# Stepper_1_0.net
KiCad netlist of a schematic drawn in EAGLE
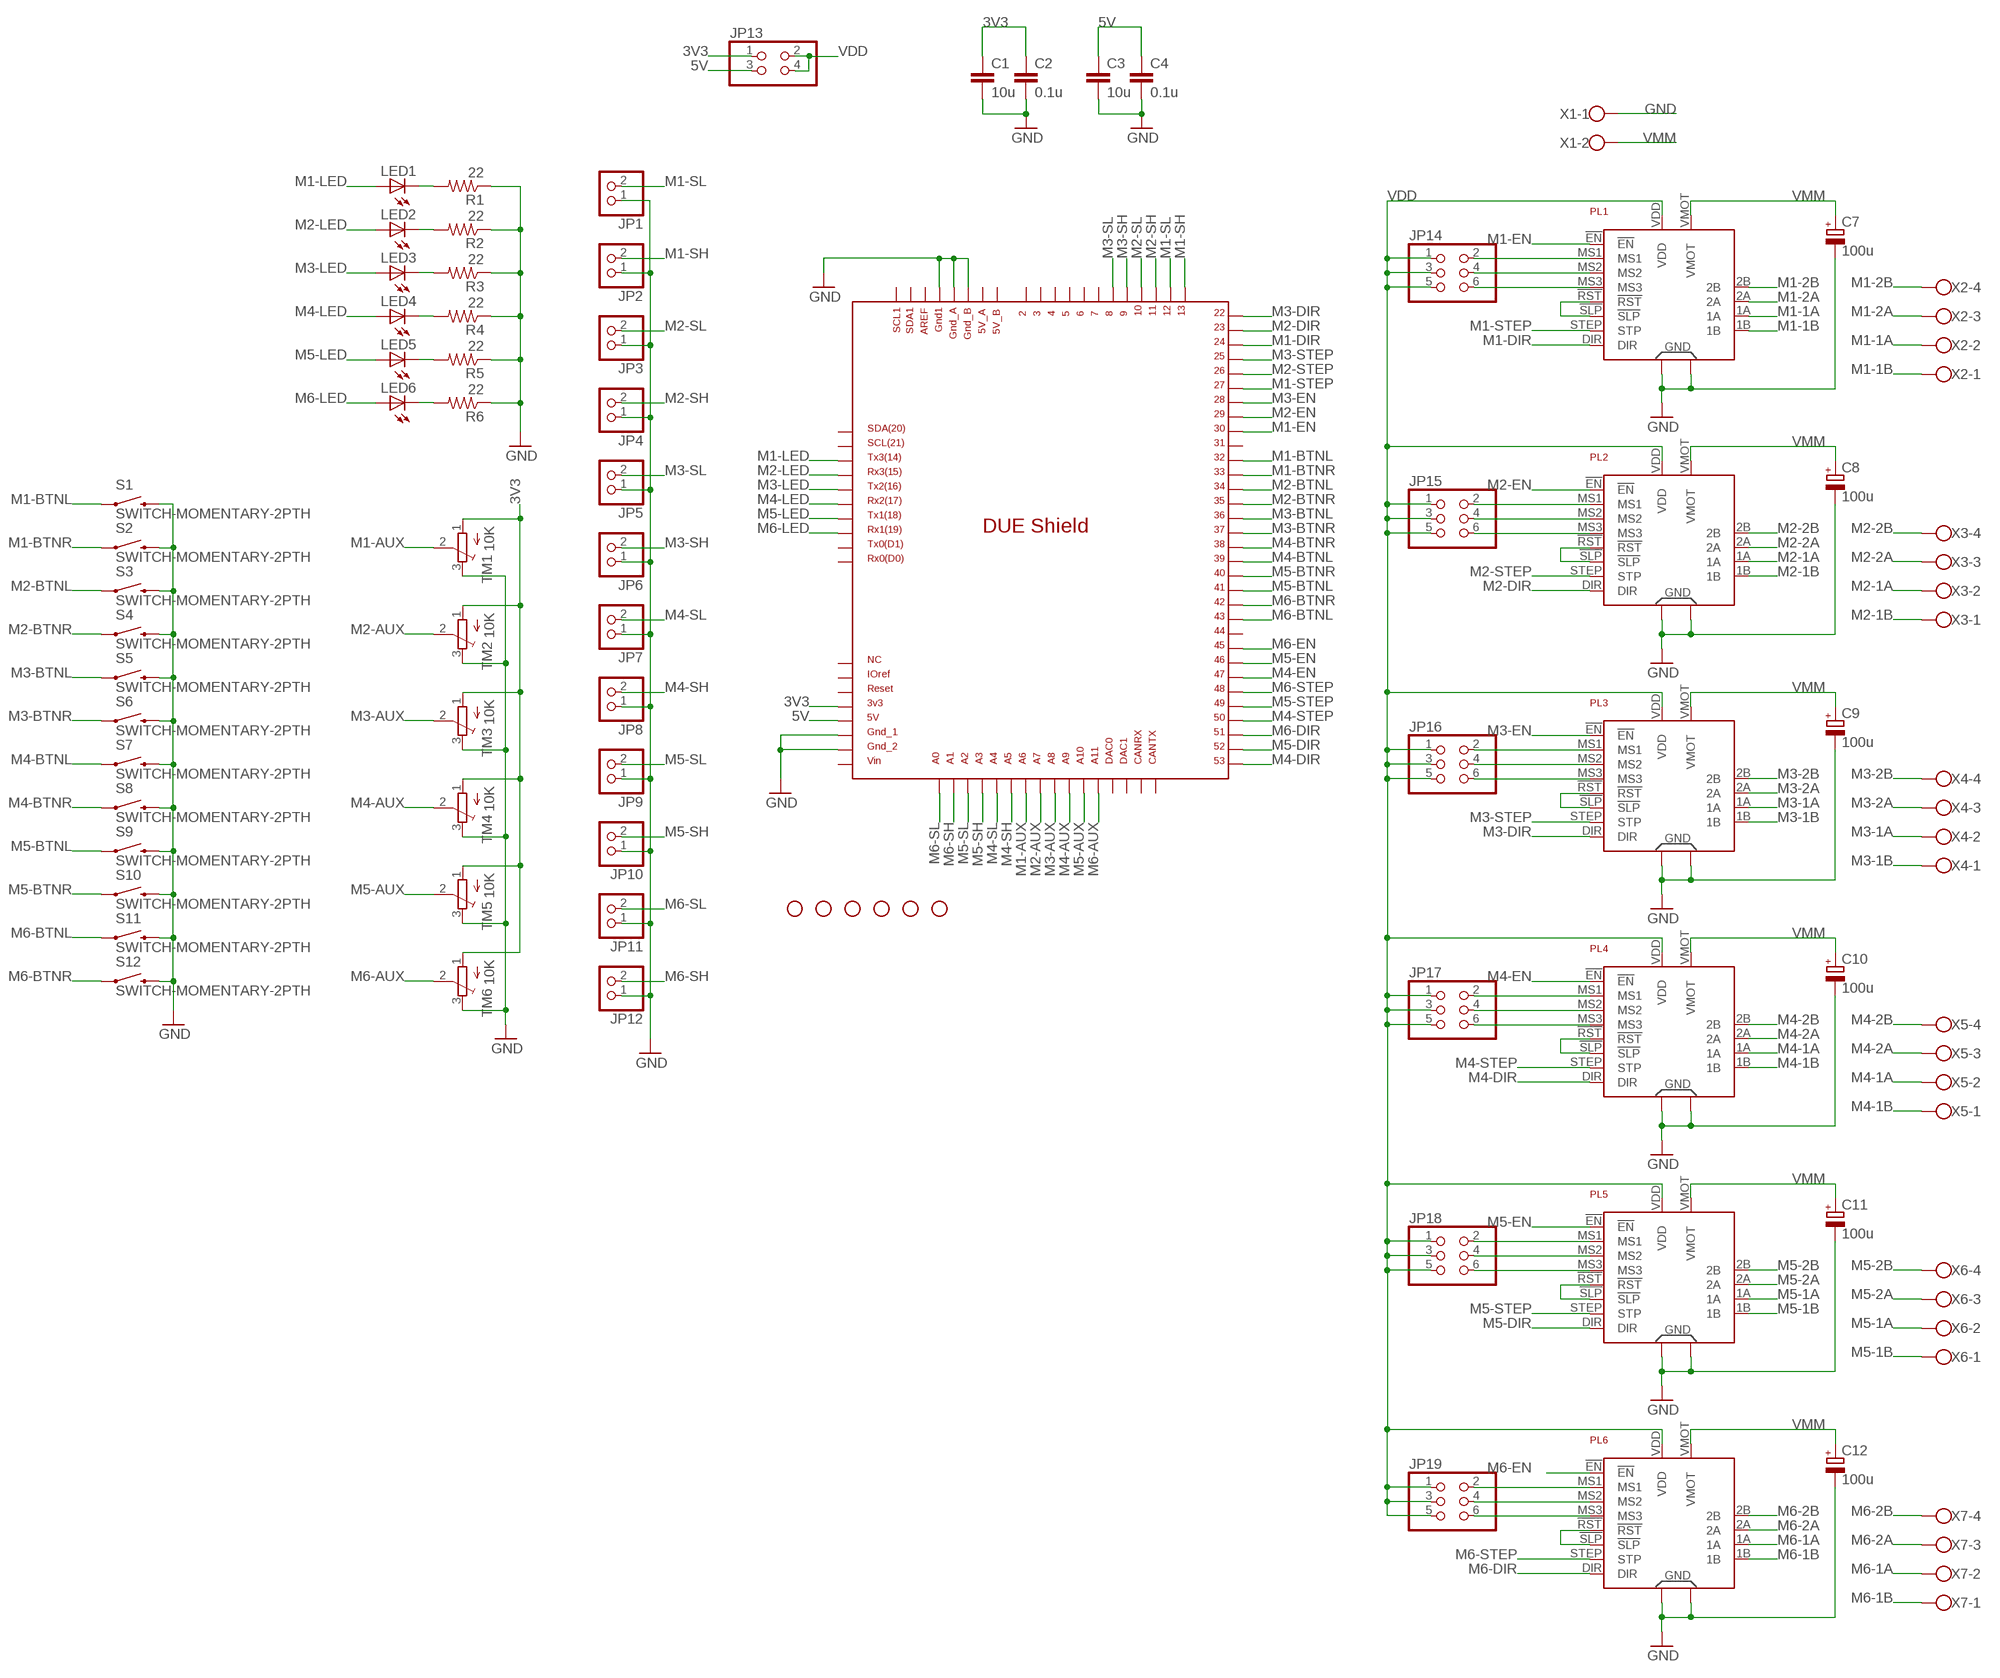
[diagram p0: schematic, sheet 1]

(export (version "E")
  (design (tool "Eeschema 10.0.6"))
  (components
    (comp (ref "C1")
      (value "10u")
      (footprint "eagle-import:1206")
      (libsource (lib "eagle-import") (part "CAP1206"))
    )
    (comp (ref "C2")
      (value "0.1u")
      (footprint "eagle-import:1206")
      (libsource (lib "eagle-import") (part "CAP1206"))
    )
    (comp (ref "C3")
      (value "10u")
      (footprint "eagle-import:1206")
      (libsource (lib "eagle-import") (part "CAP1206"))
    )
    (comp (ref "C4")
      (value "0.1u")
      (footprint "eagle-import:1206")
      (libsource (lib "eagle-import") (part "CAP1206"))
    )
    (comp (ref "C7")
      (value "100u")
      (footprint "eagle-import:ETR2")
      (libsource (lib "eagle-import") (part "CPOL-EUETR2"))
    )
    (comp (ref "C8")
      (value "100u")
      (footprint "eagle-import:ETR2")
      (libsource (lib "eagle-import") (part "CPOL-EUETR2"))
    )
    (comp (ref "C9")
      (value "100u")
      (footprint "eagle-import:ETR2")
      (libsource (lib "eagle-import") (part "CPOL-EUETR2"))
    )
    (comp (ref "C10")
      (value "100u")
      (footprint "eagle-import:ETR2")
      (libsource (lib "eagle-import") (part "CPOL-EUETR2"))
    )
    (comp (ref "C11")
      (value "100u")
      (footprint "eagle-import:ETR2")
      (libsource (lib "eagle-import") (part "CPOL-EUETR2"))
    )
    (comp (ref "C12")
      (value "100u")
      (footprint "eagle-import:ETR2")
      (libsource (lib "eagle-import") (part "CPOL-EUETR2"))
    )
    (comp (ref "H1")
      (value "STAND-OFF")
      (footprint "eagle-import:STAND-OFF")
      (libsource (lib "eagle-import") (part "STAND-OFF"))
    )
    (comp (ref "H2")
      (value "STAND-OFF")
      (footprint "eagle-import:STAND-OFF")
      (libsource (lib "eagle-import") (part "STAND-OFF"))
    )
    (comp (ref "H3")
      (value "STAND-OFF")
      (footprint "eagle-import:STAND-OFF")
      (libsource (lib "eagle-import") (part "STAND-OFF"))
    )
    (comp (ref "H4")
      (value "STAND-OFF")
      (footprint "eagle-import:STAND-OFF")
      (libsource (lib "eagle-import") (part "STAND-OFF"))
    )
    (comp (ref "H5")
      (value "STAND-OFF")
      (footprint "eagle-import:STAND-OFF")
      (libsource (lib "eagle-import") (part "STAND-OFF"))
    )
    (comp (ref "H6")
      (value "STAND-OFF")
      (footprint "eagle-import:STAND-OFF")
      (libsource (lib "eagle-import") (part "STAND-OFF"))
    )
    (comp (ref "JP1")
      (value "PINHD-1X2")
      (footprint "eagle-import:1X02")
      (libsource (lib "eagle-import") (part "PINHD-1X2"))
    )
    (comp (ref "JP2")
      (value "PINHD-1X2")
      (footprint "eagle-import:1X02")
      (libsource (lib "eagle-import") (part "PINHD-1X2"))
    )
    (comp (ref "JP3")
      (value "PINHD-1X2")
      (footprint "eagle-import:1X02")
      (libsource (lib "eagle-import") (part "PINHD-1X2"))
    )
    (comp (ref "JP4")
      (value "PINHD-1X2")
      (footprint "eagle-import:1X02")
      (libsource (lib "eagle-import") (part "PINHD-1X2"))
    )
    (comp (ref "JP5")
      (value "PINHD-1X2")
      (footprint "eagle-import:1X02")
      (libsource (lib "eagle-import") (part "PINHD-1X2"))
    )
    (comp (ref "JP6")
      (value "PINHD-1X2")
      (footprint "eagle-import:1X02")
      (libsource (lib "eagle-import") (part "PINHD-1X2"))
    )
    (comp (ref "JP7")
      (value "PINHD-1X2")
      (footprint "eagle-import:1X02")
      (libsource (lib "eagle-import") (part "PINHD-1X2"))
    )
    (comp (ref "JP8")
      (value "PINHD-1X2")
      (footprint "eagle-import:1X02")
      (libsource (lib "eagle-import") (part "PINHD-1X2"))
    )
    (comp (ref "JP9")
      (value "PINHD-1X2")
      (footprint "eagle-import:1X02")
      (libsource (lib "eagle-import") (part "PINHD-1X2"))
    )
    (comp (ref "JP10")
      (value "PINHD-1X2")
      (footprint "eagle-import:1X02")
      (libsource (lib "eagle-import") (part "PINHD-1X2"))
    )
    (comp (ref "JP11")
      (value "PINHD-1X2")
      (footprint "eagle-import:1X02")
      (libsource (lib "eagle-import") (part "PINHD-1X2"))
    )
    (comp (ref "JP12")
      (value "PINHD-1X2")
      (footprint "eagle-import:1X02")
      (libsource (lib "eagle-import") (part "PINHD-1X2"))
    )
    (comp (ref "JP13")
      (value "PINHD-2X2")
      (footprint "eagle-import:2X02")
      (libsource (lib "eagle-import") (part "PINHD-2X2"))
    )
    (comp (ref "JP14")
      (value "PINHD-2X3")
      (footprint "eagle-import:2X03")
      (libsource (lib "eagle-import") (part "PINHD-2X3"))
    )
    (comp (ref "JP15")
      (value "PINHD-2X3")
      (footprint "eagle-import:2X03")
      (libsource (lib "eagle-import") (part "PINHD-2X3"))
    )
    (comp (ref "JP16")
      (value "PINHD-2X3")
      (footprint "eagle-import:2X03")
      (libsource (lib "eagle-import") (part "PINHD-2X3"))
    )
    (comp (ref "JP17")
      (value "PINHD-2X3")
      (footprint "eagle-import:2X03")
      (libsource (lib "eagle-import") (part "PINHD-2X3"))
    )
    (comp (ref "JP18")
      (value "PINHD-2X3")
      (footprint "eagle-import:2X03")
      (libsource (lib "eagle-import") (part "PINHD-2X3"))
    )
    (comp (ref "JP19")
      (value "PINHD-2X3")
      (footprint "eagle-import:2X03")
      (libsource (lib "eagle-import") (part "PINHD-2X3"))
    )
    (comp (ref "LED1")
      (value "LEDSMT1206")
      (footprint "eagle-import:1206")
      (libsource (lib "eagle-import") (part "LEDSMT1206"))
    )
    (comp (ref "LED2")
      (value "LEDSMT1206")
      (footprint "eagle-import:1206")
      (libsource (lib "eagle-import") (part "LEDSMT1206"))
    )
    (comp (ref "LED3")
      (value "LEDSMT1206")
      (footprint "eagle-import:1206")
      (libsource (lib "eagle-import") (part "LEDSMT1206"))
    )
    (comp (ref "LED4")
      (value "LEDSMT1206")
      (footprint "eagle-import:1206")
      (libsource (lib "eagle-import") (part "LEDSMT1206"))
    )
    (comp (ref "LED5")
      (value "LEDSMT1206")
      (footprint "eagle-import:1206")
      (libsource (lib "eagle-import") (part "LEDSMT1206"))
    )
    (comp (ref "LED6")
      (value "LEDSMT1206")
      (footprint "eagle-import:1206")
      (libsource (lib "eagle-import") (part "LEDSMT1206"))
    )
    (comp (ref "PL1")
      (value "A4988X")
      (footprint "eagle-import:MD09X")
      (libsource (lib "eagle-import") (part "A4988X"))
    )
    (comp (ref "PL2")
      (value "A4988X")
      (footprint "eagle-import:MD09X")
      (libsource (lib "eagle-import") (part "A4988X"))
    )
    (comp (ref "PL3")
      (value "A4988X")
      (footprint "eagle-import:MD09X")
      (libsource (lib "eagle-import") (part "A4988X"))
    )
    (comp (ref "PL4")
      (value "A4988X")
      (footprint "eagle-import:MD09X")
      (libsource (lib "eagle-import") (part "A4988X"))
    )
    (comp (ref "PL5")
      (value "A4988X")
      (footprint "eagle-import:MD09X")
      (libsource (lib "eagle-import") (part "A4988X"))
    )
    (comp (ref "PL6")
      (value "A4988X")
      (footprint "eagle-import:MD09X")
      (libsource (lib "eagle-import") (part "A4988X"))
    )
    (comp (ref "R1")
      (value "22")
      (footprint "eagle-import:1206")
      (libsource (lib "eagle-import") (part "RESISTOR1206"))
    )
    (comp (ref "R2")
      (value "22")
      (footprint "eagle-import:1206")
      (libsource (lib "eagle-import") (part "RESISTOR1206"))
    )
    (comp (ref "R3")
      (value "22")
      (footprint "eagle-import:1206")
      (libsource (lib "eagle-import") (part "RESISTOR1206"))
    )
    (comp (ref "R4")
      (value "22")
      (footprint "eagle-import:1206")
      (libsource (lib "eagle-import") (part "RESISTOR1206"))
    )
    (comp (ref "R5")
      (value "22")
      (footprint "eagle-import:1206")
      (libsource (lib "eagle-import") (part "RESISTOR1206"))
    )
    (comp (ref "R6")
      (value "22")
      (footprint "eagle-import:1206")
      (libsource (lib "eagle-import") (part "RESISTOR1206"))
    )
    (comp (ref "S1")
      (value "SWITCH-MOMENTARY-2PTH")
      (footprint "eagle-import:TACTILE-PTH")
      (libsource (lib "eagle-import") (part "SWITCH-MOMENTARY-2PTH"))
    )
    (comp (ref "S2")
      (value "SWITCH-MOMENTARY-2PTH")
      (footprint "eagle-import:TACTILE-PTH")
      (libsource (lib "eagle-import") (part "SWITCH-MOMENTARY-2PTH"))
    )
    (comp (ref "S3")
      (value "SWITCH-MOMENTARY-2PTH")
      (footprint "eagle-import:TACTILE-PTH")
      (libsource (lib "eagle-import") (part "SWITCH-MOMENTARY-2PTH"))
    )
    (comp (ref "S4")
      (value "SWITCH-MOMENTARY-2PTH")
      (footprint "eagle-import:TACTILE-PTH")
      (libsource (lib "eagle-import") (part "SWITCH-MOMENTARY-2PTH"))
    )
    (comp (ref "S5")
      (value "SWITCH-MOMENTARY-2PTH")
      (footprint "eagle-import:TACTILE-PTH")
      (libsource (lib "eagle-import") (part "SWITCH-MOMENTARY-2PTH"))
    )
    (comp (ref "S6")
      (value "SWITCH-MOMENTARY-2PTH")
      (footprint "eagle-import:TACTILE-PTH")
      (libsource (lib "eagle-import") (part "SWITCH-MOMENTARY-2PTH"))
    )
    (comp (ref "S7")
      (value "SWITCH-MOMENTARY-2PTH")
      (footprint "eagle-import:TACTILE-PTH")
      (libsource (lib "eagle-import") (part "SWITCH-MOMENTARY-2PTH"))
    )
    (comp (ref "S8")
      (value "SWITCH-MOMENTARY-2PTH")
      (footprint "eagle-import:TACTILE-PTH")
      (libsource (lib "eagle-import") (part "SWITCH-MOMENTARY-2PTH"))
    )
    (comp (ref "S9")
      (value "SWITCH-MOMENTARY-2PTH")
      (footprint "eagle-import:TACTILE-PTH")
      (libsource (lib "eagle-import") (part "SWITCH-MOMENTARY-2PTH"))
    )
    (comp (ref "S10")
      (value "SWITCH-MOMENTARY-2PTH")
      (footprint "eagle-import:TACTILE-PTH")
      (libsource (lib "eagle-import") (part "SWITCH-MOMENTARY-2PTH"))
    )
    (comp (ref "S11")
      (value "SWITCH-MOMENTARY-2PTH")
      (footprint "eagle-import:TACTILE-PTH")
      (libsource (lib "eagle-import") (part "SWITCH-MOMENTARY-2PTH"))
    )
    (comp (ref "S12")
      (value "SWITCH-MOMENTARY-2PTH")
      (footprint "eagle-import:TACTILE-PTH")
      (libsource (lib "eagle-import") (part "SWITCH-MOMENTARY-2PTH"))
    )
    (comp (ref "SH1")
      (value "DUE(NOSPI)")
      (footprint "eagle-import:DUE(NOSPI)")
      (libsource (lib "eagle-import") (part "DUE(NOSPI)"))
    )
    (comp (ref "TM1")
      (value "10K")
      (footprint "eagle-import:TC33X")
      (libsource (lib "eagle-import") (part "TRIMPOTTC33X"))
    )
    (comp (ref "TM2")
      (value "10K")
      (footprint "eagle-import:TC33X")
      (libsource (lib "eagle-import") (part "TRIMPOTTC33X"))
    )
    (comp (ref "TM3")
      (value "10K")
      (footprint "eagle-import:TC33X")
      (libsource (lib "eagle-import") (part "TRIMPOTTC33X"))
    )
    (comp (ref "TM4")
      (value "10K")
      (footprint "eagle-import:TC33X")
      (libsource (lib "eagle-import") (part "TRIMPOTTC33X"))
    )
    (comp (ref "TM5")
      (value "10K")
      (footprint "eagle-import:TC33X")
      (libsource (lib "eagle-import") (part "TRIMPOTTC33X"))
    )
    (comp (ref "TM6")
      (value "10K")
      (footprint "eagle-import:TC33X")
      (libsource (lib "eagle-import") (part "TRIMPOTTC33X"))
    )
    (comp (ref "X1")
      (value "W237-102")
      (footprint "eagle-import:W237-102")
      (fields (field (name "MPN") "237-102"))
      (libsource (lib "eagle-import") (part "W237-102"))
    )
    (comp (ref "X2")
      (value "W237-4")
      (footprint "eagle-import:W237-4")
      (libsource (lib "eagle-import") (part "W237-4"))
    )
    (comp (ref "X3")
      (value "W237-4")
      (footprint "eagle-import:W237-4")
      (libsource (lib "eagle-import") (part "W237-4"))
    )
    (comp (ref "X4")
      (value "W237-4")
      (footprint "eagle-import:W237-4")
      (libsource (lib "eagle-import") (part "W237-4"))
    )
    (comp (ref "X5")
      (value "W237-4")
      (footprint "eagle-import:W237-4")
      (libsource (lib "eagle-import") (part "W237-4"))
    )
    (comp (ref "X6")
      (value "W237-4")
      (footprint "eagle-import:W237-4")
      (libsource (lib "eagle-import") (part "W237-4"))
    )
    (comp (ref "X7")
      (value "W237-4")
      (footprint "eagle-import:W237-4")
      (libsource (lib "eagle-import") (part "W237-4"))
    )
  )
  (nets
    (net (code "1") (name "/3V3") (class "Default")
      (node (ref "C1") (pin "1") (pinfunction "1_1") (pintype "passive"))
      (node (ref "C2") (pin "1") (pinfunction "1_1") (pintype "passive"))
      (node (ref "JP13") (pin "1") (pinfunction "1_1") (pintype "passive"))
      (node (ref "SH1") (pin "3V3") (pinfunction "3V3_3V3") (pintype "bidirectional"))
      (node (ref "TM1") (pin "1") (pinfunction "A_1") (pintype "passive"))
      (node (ref "TM2") (pin "1") (pinfunction "A_1") (pintype "passive"))
      (node (ref "TM3") (pin "1") (pinfunction "A_1") (pintype "passive"))
      (node (ref "TM4") (pin "1") (pinfunction "A_1") (pintype "passive"))
      (node (ref "TM5") (pin "1") (pinfunction "A_1") (pintype "passive"))
      (node (ref "TM6") (pin "1") (pinfunction "A_1") (pintype "passive"))
    )
    (net (code "2") (name "/5V") (class "Default")
      (node (ref "C3") (pin "1") (pinfunction "1_1") (pintype "passive"))
      (node (ref "C4") (pin "1") (pinfunction "1_1") (pintype "passive"))
      (node (ref "JP13") (pin "3") (pinfunction "3_3") (pintype "passive"))
      (node (ref "SH1") (pin "5V") (pinfunction "5V_5V") (pintype "bidirectional"))
    )
    (net (code "3") (name "/M1-1A") (class "Default")
      (node (ref "PL1") (pin "1A") (pinfunction "1A_1A") (pintype "bidirectional"))
      (node (ref "X2") (pin "2") (pinfunction "KL_2") (pintype "passive"))
    )
    (net (code "4") (name "/M1-1B") (class "Default")
      (node (ref "PL1") (pin "1B") (pinfunction "1B_1B") (pintype "bidirectional"))
      (node (ref "X2") (pin "1") (pinfunction "KL_1") (pintype "passive"))
    )
    (net (code "5") (name "/M1-2A") (class "Default")
      (node (ref "PL1") (pin "2A") (pinfunction "2A_2A") (pintype "bidirectional"))
      (node (ref "X2") (pin "3") (pinfunction "KL_3") (pintype "passive"))
    )
    (net (code "6") (name "/M1-2B") (class "Default")
      (node (ref "PL1") (pin "2B") (pinfunction "2B_2B") (pintype "bidirectional"))
      (node (ref "X2") (pin "4") (pinfunction "KL_4") (pintype "passive"))
    )
    (net (code "7") (name "/M1-AUX") (class "Default")
      (node (ref "SH1") (pin "A6") (pinfunction "A6_A6") (pintype "bidirectional"))
      (node (ref "TM1") (pin "2") (pinfunction "S_2") (pintype "passive"))
    )
    (net (code "8") (name "/M1-BTNL") (class "Default")
      (node (ref "S1") (pin "1") (pinfunction "1_1") (pintype "passive"))
      (node (ref "SH1") (pin "32") (pinfunction "32_32") (pintype "bidirectional"))
    )
    (net (code "9") (name "/M1-BTNR") (class "Default")
      (node (ref "S2") (pin "1") (pinfunction "1_1") (pintype "passive"))
      (node (ref "SH1") (pin "33") (pinfunction "33_33") (pintype "bidirectional"))
    )
    (net (code "10") (name "/M1-DIR") (class "Default")
      (node (ref "PL1") (pin "DIR") (pinfunction "DIR_DIR") (pintype "bidirectional"))
      (node (ref "SH1") (pin "24") (pinfunction "24_24") (pintype "bidirectional"))
    )
    (net (code "11") (name "/M1-EN") (class "Default")
      (node (ref "PL1") (pin "!EN") (pinfunction "~{EN}_!EN") (pintype "bidirectional"))
      (node (ref "SH1") (pin "30") (pinfunction "30_30") (pintype "bidirectional"))
    )
    (net (code "12") (name "/M1-LED") (class "Default")
      (node (ref "LED1") (pin "A") (pinfunction "A_A") (pintype "passive"))
      (node (ref "SH1") (pin "TX3") (pinfunction "TX3_TX3") (pintype "bidirectional"))
    )
    (net (code "13") (name "/M1-SH") (class "Default")
      (node (ref "JP2") (pin "2") (pinfunction "2_2") (pintype "passive"))
      (node (ref "SH1") (pin "13") (pinfunction "13_13") (pintype "bidirectional"))
    )
    (net (code "14") (name "/M1-SL") (class "Default")
      (node (ref "JP1") (pin "2") (pinfunction "2_2") (pintype "passive"))
      (node (ref "SH1") (pin "12") (pinfunction "12_12") (pintype "bidirectional"))
    )
    (net (code "15") (name "/M1-STEP") (class "Default")
      (node (ref "PL1") (pin "STEP") (pinfunction "STP_STEP") (pintype "bidirectional"))
      (node (ref "SH1") (pin "27") (pinfunction "27_27") (pintype "bidirectional"))
    )
    (net (code "16") (name "/M2-1A") (class "Default")
      (node (ref "PL2") (pin "1A") (pinfunction "1A_1A") (pintype "bidirectional"))
      (node (ref "X3") (pin "2") (pinfunction "KL_2") (pintype "passive"))
    )
    (net (code "17") (name "/M2-1B") (class "Default")
      (node (ref "PL2") (pin "1B") (pinfunction "1B_1B") (pintype "bidirectional"))
      (node (ref "X3") (pin "1") (pinfunction "KL_1") (pintype "passive"))
    )
    (net (code "18") (name "/M2-2A") (class "Default")
      (node (ref "PL2") (pin "2A") (pinfunction "2A_2A") (pintype "bidirectional"))
      (node (ref "X3") (pin "3") (pinfunction "KL_3") (pintype "passive"))
    )
    (net (code "19") (name "/M2-2B") (class "Default")
      (node (ref "PL2") (pin "2B") (pinfunction "2B_2B") (pintype "bidirectional"))
      (node (ref "X3") (pin "4") (pinfunction "KL_4") (pintype "passive"))
    )
    (net (code "20") (name "/M2-AUX") (class "Default")
      (node (ref "SH1") (pin "A7") (pinfunction "A7_A7") (pintype "bidirectional"))
      (node (ref "TM2") (pin "2") (pinfunction "S_2") (pintype "passive"))
    )
    (net (code "21") (name "/M2-BTNL") (class "Default")
      (node (ref "S3") (pin "1") (pinfunction "1_1") (pintype "passive"))
      (node (ref "SH1") (pin "34") (pinfunction "34_34") (pintype "bidirectional"))
    )
    (net (code "22") (name "/M2-BTNR") (class "Default")
      (node (ref "S4") (pin "1") (pinfunction "1_1") (pintype "passive"))
      (node (ref "SH1") (pin "35") (pinfunction "35_35") (pintype "bidirectional"))
    )
    (net (code "23") (name "/M2-DIR") (class "Default")
      (node (ref "PL2") (pin "DIR") (pinfunction "DIR_DIR") (pintype "bidirectional"))
      (node (ref "SH1") (pin "23") (pinfunction "23_23") (pintype "bidirectional"))
    )
    (net (code "24") (name "/M2-EN") (class "Default")
      (node (ref "PL2") (pin "!EN") (pinfunction "~{EN}_!EN") (pintype "bidirectional"))
      (node (ref "SH1") (pin "29") (pinfunction "29_29") (pintype "bidirectional"))
    )
    (net (code "25") (name "/M2-LED") (class "Default")
      (node (ref "LED2") (pin "A") (pinfunction "A_A") (pintype "passive"))
      (node (ref "SH1") (pin "RX3") (pinfunction "RX3_RX3") (pintype "bidirectional"))
    )
    (net (code "26") (name "/M2-SH") (class "Default")
      (node (ref "JP4") (pin "2") (pinfunction "2_2") (pintype "passive"))
      (node (ref "SH1") (pin "11") (pinfunction "11_11") (pintype "bidirectional"))
    )
    (net (code "27") (name "/M2-SL") (class "Default")
      (node (ref "JP3") (pin "2") (pinfunction "2_2") (pintype "passive"))
      (node (ref "SH1") (pin "10") (pinfunction "10_10") (pintype "bidirectional"))
    )
    (net (code "28") (name "/M2-STEP") (class "Default")
      (node (ref "PL2") (pin "STEP") (pinfunction "STP_STEP") (pintype "bidirectional"))
      (node (ref "SH1") (pin "26") (pinfunction "26_26") (pintype "bidirectional"))
    )
    (net (code "29") (name "/M3-1A") (class "Default")
      (node (ref "PL3") (pin "1A") (pinfunction "1A_1A") (pintype "bidirectional"))
      (node (ref "X4") (pin "2") (pinfunction "KL_2") (pintype "passive"))
    )
    (net (code "30") (name "/M3-1B") (class "Default")
      (node (ref "PL3") (pin "1B") (pinfunction "1B_1B") (pintype "bidirectional"))
      (node (ref "X4") (pin "1") (pinfunction "KL_1") (pintype "passive"))
    )
    (net (code "31") (name "/M3-2A") (class "Default")
      (node (ref "PL3") (pin "2A") (pinfunction "2A_2A") (pintype "bidirectional"))
      (node (ref "X4") (pin "3") (pinfunction "KL_3") (pintype "passive"))
    )
    (net (code "32") (name "/M3-2B") (class "Default")
      (node (ref "PL3") (pin "2B") (pinfunction "2B_2B") (pintype "bidirectional"))
      (node (ref "X4") (pin "4") (pinfunction "KL_4") (pintype "passive"))
    )
    (net (code "33") (name "/M3-AUX") (class "Default")
      (node (ref "SH1") (pin "A8") (pinfunction "A8_A8") (pintype "bidirectional"))
      (node (ref "TM3") (pin "2") (pinfunction "S_2") (pintype "passive"))
    )
    (net (code "34") (name "/M3-BTNL") (class "Default")
      (node (ref "S5") (pin "1") (pinfunction "1_1") (pintype "passive"))
      (node (ref "SH1") (pin "36") (pinfunction "36_36") (pintype "bidirectional"))
    )
    (net (code "35") (name "/M3-BTNR") (class "Default")
      (node (ref "S6") (pin "1") (pinfunction "1_1") (pintype "passive"))
      (node (ref "SH1") (pin "37") (pinfunction "37_37") (pintype "bidirectional"))
    )
    (net (code "36") (name "/M3-DIR") (class "Default")
      (node (ref "PL3") (pin "DIR") (pinfunction "DIR_DIR") (pintype "bidirectional"))
      (node (ref "SH1") (pin "22") (pinfunction "22_22") (pintype "bidirectional"))
    )
    (net (code "37") (name "/M3-EN") (class "Default")
      (node (ref "PL3") (pin "!EN") (pinfunction "~{EN}_!EN") (pintype "bidirectional"))
      (node (ref "SH1") (pin "28") (pinfunction "28_28") (pintype "bidirectional"))
    )
    (net (code "38") (name "/M3-LED") (class "Default")
      (node (ref "LED3") (pin "A") (pinfunction "A_A") (pintype "passive"))
      (node (ref "SH1") (pin "TX2") (pinfunction "TX2_TX2") (pintype "bidirectional"))
    )
    (net (code "39") (name "/M3-SH") (class "Default")
      (node (ref "JP6") (pin "2") (pinfunction "2_2") (pintype "passive"))
      (node (ref "SH1") (pin "9") (pinfunction "9_9") (pintype "bidirectional"))
    )
    (net (code "40") (name "/M3-SL") (class "Default")
      (node (ref "JP5") (pin "2") (pinfunction "2_2") (pintype "passive"))
      (node (ref "SH1") (pin "8") (pinfunction "8_8") (pintype "bidirectional"))
    )
    (net (code "41") (name "/M3-STEP") (class "Default")
      (node (ref "PL3") (pin "STEP") (pinfunction "STP_STEP") (pintype "bidirectional"))
      (node (ref "SH1") (pin "25") (pinfunction "25_25") (pintype "bidirectional"))
    )
    (net (code "42") (name "/M4-1A") (class "Default")
      (node (ref "PL4") (pin "1A") (pinfunction "1A_1A") (pintype "bidirectional"))
      (node (ref "X5") (pin "2") (pinfunction "KL_2") (pintype "passive"))
    )
    (net (code "43") (name "/M4-1B") (class "Default")
      (node (ref "PL4") (pin "1B") (pinfunction "1B_1B") (pintype "bidirectional"))
      (node (ref "X5") (pin "1") (pinfunction "KL_1") (pintype "passive"))
    )
    (net (code "44") (name "/M4-2A") (class "Default")
      (node (ref "PL4") (pin "2A") (pinfunction "2A_2A") (pintype "bidirectional"))
      (node (ref "X5") (pin "3") (pinfunction "KL_3") (pintype "passive"))
    )
    (net (code "45") (name "/M4-2B") (class "Default")
      (node (ref "PL4") (pin "2B") (pinfunction "2B_2B") (pintype "bidirectional"))
      (node (ref "X5") (pin "4") (pinfunction "KL_4") (pintype "passive"))
    )
    (net (code "46") (name "/M4-AUX") (class "Default")
      (node (ref "SH1") (pin "A9") (pinfunction "A9_A9") (pintype "bidirectional"))
      (node (ref "TM4") (pin "2") (pinfunction "S_2") (pintype "passive"))
    )
    (net (code "47") (name "/M4-BTNL") (class "Default")
      (node (ref "S7") (pin "1") (pinfunction "1_1") (pintype "passive"))
      (node (ref "SH1") (pin "39") (pinfunction "39_39") (pintype "bidirectional"))
    )
    (net (code "48") (name "/M4-BTNR") (class "Default")
      (node (ref "S8") (pin "1") (pinfunction "1_1") (pintype "passive"))
      (node (ref "SH1") (pin "38") (pinfunction "38_38") (pintype "bidirectional"))
    )
    (net (code "49") (name "/M4-DIR") (class "Default")
      (node (ref "PL4") (pin "DIR") (pinfunction "DIR_DIR") (pintype "bidirectional"))
      (node (ref "SH1") (pin "53") (pinfunction "53_53") (pintype "bidirectional"))
    )
    (net (code "50") (name "/M4-EN") (class "Default")
      (node (ref "PL4") (pin "!EN") (pinfunction "~{EN}_!EN") (pintype "bidirectional"))
      (node (ref "SH1") (pin "47") (pinfunction "47_47") (pintype "bidirectional"))
    )
    (net (code "51") (name "/M4-LED") (class "Default")
      (node (ref "LED4") (pin "A") (pinfunction "A_A") (pintype "passive"))
      (node (ref "SH1") (pin "RX2") (pinfunction "RX2_RX2") (pintype "bidirectional"))
    )
    (net (code "52") (name "/M4-SH") (class "Default")
      (node (ref "JP8") (pin "2") (pinfunction "2_2") (pintype "passive"))
      (node (ref "SH1") (pin "A5") (pinfunction "A5_A5") (pintype "bidirectional"))
    )
    (net (code "53") (name "/M4-SL") (class "Default")
      (node (ref "JP7") (pin "2") (pinfunction "2_2") (pintype "passive"))
      (node (ref "SH1") (pin "A4") (pinfunction "A4_A4") (pintype "bidirectional"))
    )
    (net (code "54") (name "/M4-STEP") (class "Default")
      (node (ref "PL4") (pin "STEP") (pinfunction "STP_STEP") (pintype "bidirectional"))
      (node (ref "SH1") (pin "50") (pinfunction "50_50") (pintype "bidirectional"))
    )
    (net (code "55") (name "/M5-1A") (class "Default")
      (node (ref "PL5") (pin "1A") (pinfunction "1A_1A") (pintype "bidirectional"))
      (node (ref "X6") (pin "2") (pinfunction "KL_2") (pintype "passive"))
    )
    (net (code "56") (name "/M5-1B") (class "Default")
      (node (ref "PL5") (pin "1B") (pinfunction "1B_1B") (pintype "bidirectional"))
      (node (ref "X6") (pin "1") (pinfunction "KL_1") (pintype "passive"))
    )
    (net (code "57") (name "/M5-2A") (class "Default")
      (node (ref "PL5") (pin "2A") (pinfunction "2A_2A") (pintype "bidirectional"))
      (node (ref "X6") (pin "3") (pinfunction "KL_3") (pintype "passive"))
    )
    (net (code "58") (name "/M5-2B") (class "Default")
      (node (ref "PL5") (pin "2B") (pinfunction "2B_2B") (pintype "bidirectional"))
      (node (ref "X6") (pin "4") (pinfunction "KL_4") (pintype "passive"))
    )
    (net (code "59") (name "/M5-AUX") (class "Default")
      (node (ref "SH1") (pin "A10") (pinfunction "A10_A10") (pintype "bidirectional"))
      (node (ref "TM5") (pin "2") (pinfunction "S_2") (pintype "passive"))
    )
    (net (code "60") (name "/M5-BTNL") (class "Default")
      (node (ref "S9") (pin "1") (pinfunction "1_1") (pintype "passive"))
      (node (ref "SH1") (pin "41") (pinfunction "41_41") (pintype "bidirectional"))
    )
    (net (code "61") (name "/M5-BTNR") (class "Default")
      (node (ref "S10") (pin "1") (pinfunction "1_1") (pintype "passive"))
      (node (ref "SH1") (pin "40") (pinfunction "40_40") (pintype "bidirectional"))
    )
    (net (code "62") (name "/M5-DIR") (class "Default")
      (node (ref "PL5") (pin "DIR") (pinfunction "DIR_DIR") (pintype "bidirectional"))
      (node (ref "SH1") (pin "52") (pinfunction "52_52") (pintype "bidirectional"))
    )
    (net (code "63") (name "/M5-EN") (class "Default")
      (node (ref "PL5") (pin "!EN") (pinfunction "~{EN}_!EN") (pintype "bidirectional"))
      (node (ref "SH1") (pin "46") (pinfunction "46_46") (pintype "bidirectional"))
    )
    (net (code "64") (name "/M5-LED") (class "Default")
      (node (ref "LED5") (pin "A") (pinfunction "A_A") (pintype "passive"))
      (node (ref "SH1") (pin "TX1") (pinfunction "TX1_TX1") (pintype "bidirectional"))
    )
    (net (code "65") (name "/M5-SH") (class "Default")
      (node (ref "JP10") (pin "2") (pinfunction "2_2") (pintype "passive"))
      (node (ref "SH1") (pin "A3") (pinfunction "A3_A3") (pintype "bidirectional"))
    )
    (net (code "66") (name "/M5-SL") (class "Default")
      (node (ref "JP9") (pin "2") (pinfunction "2_2") (pintype "passive"))
      (node (ref "SH1") (pin "A2") (pinfunction "A2_A2") (pintype "bidirectional"))
    )
    (net (code "67") (name "/M5-STEP") (class "Default")
      (node (ref "PL5") (pin "STEP") (pinfunction "STP_STEP") (pintype "bidirectional"))
      (node (ref "SH1") (pin "49") (pinfunction "49_49") (pintype "bidirectional"))
    )
    (net (code "68") (name "/M6-1A") (class "Default")
      (node (ref "PL6") (pin "1A") (pinfunction "1A_1A") (pintype "bidirectional"))
      (node (ref "X7") (pin "2") (pinfunction "KL_2") (pintype "passive"))
    )
    (net (code "69") (name "/M6-1B") (class "Default")
      (node (ref "PL6") (pin "1B") (pinfunction "1B_1B") (pintype "bidirectional"))
      (node (ref "X7") (pin "1") (pinfunction "KL_1") (pintype "passive"))
    )
    (net (code "70") (name "/M6-2A") (class "Default")
      (node (ref "PL6") (pin "2A") (pinfunction "2A_2A") (pintype "bidirectional"))
      (node (ref "X7") (pin "3") (pinfunction "KL_3") (pintype "passive"))
    )
    (net (code "71") (name "/M6-2B") (class "Default")
      (node (ref "PL6") (pin "2B") (pinfunction "2B_2B") (pintype "bidirectional"))
      (node (ref "X7") (pin "4") (pinfunction "KL_4") (pintype "passive"))
    )
    (net (code "72") (name "/M6-AUX") (class "Default")
      (node (ref "SH1") (pin "A11") (pinfunction "A11_A11") (pintype "bidirectional"))
      (node (ref "TM6") (pin "2") (pinfunction "S_2") (pintype "passive"))
    )
    (net (code "73") (name "/M6-BTNL") (class "Default")
      (node (ref "S11") (pin "1") (pinfunction "1_1") (pintype "passive"))
      (node (ref "SH1") (pin "43") (pinfunction "43_43") (pintype "bidirectional"))
    )
    (net (code "74") (name "/M6-BTNR") (class "Default")
      (node (ref "S12") (pin "1") (pinfunction "1_1") (pintype "passive"))
      (node (ref "SH1") (pin "42") (pinfunction "42_42") (pintype "bidirectional"))
    )
    (net (code "75") (name "/M6-DIR") (class "Default")
      (node (ref "PL6") (pin "DIR") (pinfunction "DIR_DIR") (pintype "bidirectional"))
      (node (ref "SH1") (pin "51") (pinfunction "51_51") (pintype "bidirectional"))
    )
    (net (code "76") (name "/M6-EN") (class "Default")
      (node (ref "PL6") (pin "!EN") (pinfunction "~{EN}_!EN") (pintype "bidirectional"))
      (node (ref "SH1") (pin "45") (pinfunction "45_45") (pintype "bidirectional"))
    )
    (net (code "77") (name "/M6-LED") (class "Default")
      (node (ref "LED6") (pin "A") (pinfunction "A_A") (pintype "passive"))
      (node (ref "SH1") (pin "RX1") (pinfunction "RX1_RX1") (pintype "bidirectional"))
    )
    (net (code "78") (name "/M6-SH") (class "Default")
      (node (ref "JP12") (pin "2") (pinfunction "2_2") (pintype "passive"))
      (node (ref "SH1") (pin "A1") (pinfunction "A1_A1") (pintype "bidirectional"))
    )
    (net (code "79") (name "/M6-SL") (class "Default")
      (node (ref "JP11") (pin "2") (pinfunction "2_2") (pintype "passive"))
      (node (ref "SH1") (pin "A0") (pinfunction "A0_A0") (pintype "bidirectional"))
    )
    (net (code "80") (name "/M6-STEP") (class "Default")
      (node (ref "PL6") (pin "STEP") (pinfunction "STP_STEP") (pintype "bidirectional"))
      (node (ref "SH1") (pin "48") (pinfunction "48_48") (pintype "bidirectional"))
    )
    (net (code "81") (name "/VDD") (class "Default")
      (node (ref "JP13") (pin "2") (pinfunction "2_2") (pintype "passive"))
      (node (ref "JP13") (pin "4") (pinfunction "4_4") (pintype "passive"))
      (node (ref "JP14") (pin "1") (pinfunction "1_1") (pintype "passive"))
      (node (ref "JP14") (pin "3") (pinfunction "3_3") (pintype "passive"))
      (node (ref "JP14") (pin "5") (pinfunction "5_5") (pintype "passive"))
      (node (ref "JP15") (pin "1") (pinfunction "1_1") (pintype "passive"))
      (node (ref "JP15") (pin "3") (pinfunction "3_3") (pintype "passive"))
      (node (ref "JP15") (pin "5") (pinfunction "5_5") (pintype "passive"))
      (node (ref "JP16") (pin "1") (pinfunction "1_1") (pintype "passive"))
      (node (ref "JP16") (pin "3") (pinfunction "3_3") (pintype "passive"))
      (node (ref "JP16") (pin "5") (pinfunction "5_5") (pintype "passive"))
      (node (ref "JP17") (pin "1") (pinfunction "1_1") (pintype "passive"))
      (node (ref "JP17") (pin "3") (pinfunction "3_3") (pintype "passive"))
      (node (ref "JP17") (pin "5") (pinfunction "5_5") (pintype "passive"))
      (node (ref "JP18") (pin "1") (pinfunction "1_1") (pintype "passive"))
      (node (ref "JP18") (pin "3") (pinfunction "3_3") (pintype "passive"))
      (node (ref "JP18") (pin "5") (pinfunction "5_5") (pintype "passive"))
      (node (ref "JP19") (pin "1") (pinfunction "1_1") (pintype "passive"))
      (node (ref "JP19") (pin "3") (pinfunction "3_3") (pintype "passive"))
      (node (ref "JP19") (pin "5") (pinfunction "5_5") (pintype "passive"))
      (node (ref "PL1") (pin "VDD") (pinfunction "VDD_VDD") (pintype "bidirectional"))
      (node (ref "PL2") (pin "VDD") (pinfunction "VDD_VDD") (pintype "bidirectional"))
      (node (ref "PL3") (pin "VDD") (pinfunction "VDD_VDD") (pintype "bidirectional"))
      (node (ref "PL4") (pin "VDD") (pinfunction "VDD_VDD") (pintype "bidirectional"))
      (node (ref "PL5") (pin "VDD") (pinfunction "VDD_VDD") (pintype "bidirectional"))
      (node (ref "PL6") (pin "VDD") (pinfunction "VDD_VDD") (pintype "bidirectional"))
    )
    (net (code "82") (name "/VMM") (class "Default")
      (node (ref "C10") (pin "+") (pinfunction "+_+") (pintype "passive"))
      (node (ref "C11") (pin "+") (pinfunction "+_+") (pintype "passive"))
      (node (ref "C12") (pin "+") (pinfunction "+_+") (pintype "passive"))
      (node (ref "C7") (pin "+") (pinfunction "+_+") (pintype "passive"))
      (node (ref "C8") (pin "+") (pinfunction "+_+") (pintype "passive"))
      (node (ref "C9") (pin "+") (pinfunction "+_+") (pintype "passive"))
      (node (ref "PL1") (pin "VMOT") (pinfunction "VMOT_VMOT") (pintype "bidirectional"))
      (node (ref "PL2") (pin "VMOT") (pinfunction "VMOT_VMOT") (pintype "bidirectional"))
      (node (ref "PL3") (pin "VMOT") (pinfunction "VMOT_VMOT") (pintype "bidirectional"))
      (node (ref "PL4") (pin "VMOT") (pinfunction "VMOT_VMOT") (pintype "bidirectional"))
      (node (ref "PL5") (pin "VMOT") (pinfunction "VMOT_VMOT") (pintype "bidirectional"))
      (node (ref "PL6") (pin "VMOT") (pinfunction "VMOT_VMOT") (pintype "bidirectional"))
      (node (ref "X1") (pin "2") (pinfunction "KL_2") (pintype "passive"))
    )
    (net (code "83") (name "GND") (class "Default")
      (node (ref "C1") (pin "2") (pinfunction "2_2") (pintype "passive"))
      (node (ref "C10") (pin "-") (pinfunction "-_-") (pintype "passive"))
      (node (ref "C11") (pin "-") (pinfunction "-_-") (pintype "passive"))
      (node (ref "C12") (pin "-") (pinfunction "-_-") (pintype "passive"))
      (node (ref "C2") (pin "2") (pinfunction "2_2") (pintype "passive"))
      (node (ref "C3") (pin "2") (pinfunction "2_2") (pintype "passive"))
      (node (ref "C4") (pin "2") (pinfunction "2_2") (pintype "passive"))
      (node (ref "C7") (pin "-") (pinfunction "-_-") (pintype "passive"))
      (node (ref "C8") (pin "-") (pinfunction "-_-") (pintype "passive"))
      (node (ref "C9") (pin "-") (pinfunction "-_-") (pintype "passive"))
      (node (ref "JP1") (pin "1") (pinfunction "1_1") (pintype "passive"))
      (node (ref "JP10") (pin "1") (pinfunction "1_1") (pintype "passive"))
      (node (ref "JP11") (pin "1") (pinfunction "1_1") (pintype "passive"))
      (node (ref "JP12") (pin "1") (pinfunction "1_1") (pintype "passive"))
      (node (ref "JP2") (pin "1") (pinfunction "1_1") (pintype "passive"))
      (node (ref "JP3") (pin "1") (pinfunction "1_1") (pintype "passive"))
      (node (ref "JP4") (pin "1") (pinfunction "1_1") (pintype "passive"))
      (node (ref "JP5") (pin "1") (pinfunction "1_1") (pintype "passive"))
      (node (ref "JP6") (pin "1") (pinfunction "1_1") (pintype "passive"))
      (node (ref "JP7") (pin "1") (pinfunction "1_1") (pintype "passive"))
      (node (ref "JP8") (pin "1") (pinfunction "1_1") (pintype "passive"))
      (node (ref "JP9") (pin "1") (pinfunction "1_1") (pintype "passive"))
      (node (ref "PL1") (pin "GND1") (pinfunction "GND1_GND1") (pintype "bidirectional"))
      (node (ref "PL1") (pin "GND2") (pinfunction "GND2_GND2") (pintype "bidirectional"))
      (node (ref "PL2") (pin "GND1") (pinfunction "GND1_GND1") (pintype "bidirectional"))
      (node (ref "PL2") (pin "GND2") (pinfunction "GND2_GND2") (pintype "bidirectional"))
      (node (ref "PL3") (pin "GND1") (pinfunction "GND1_GND1") (pintype "bidirectional"))
      (node (ref "PL3") (pin "GND2") (pinfunction "GND2_GND2") (pintype "bidirectional"))
      (node (ref "PL4") (pin "GND1") (pinfunction "GND1_GND1") (pintype "bidirectional"))
      (node (ref "PL4") (pin "GND2") (pinfunction "GND2_GND2") (pintype "bidirectional"))
      (node (ref "PL5") (pin "GND1") (pinfunction "GND1_GND1") (pintype "bidirectional"))
      (node (ref "PL5") (pin "GND2") (pinfunction "GND2_GND2") (pintype "bidirectional"))
      (node (ref "PL6") (pin "GND1") (pinfunction "GND1_GND1") (pintype "bidirectional"))
      (node (ref "PL6") (pin "GND2") (pinfunction "GND2_GND2") (pintype "bidirectional"))
      (node (ref "R1") (pin "1") (pinfunction "1_1") (pintype "passive"))
      (node (ref "R2") (pin "1") (pinfunction "1_1") (pintype "passive"))
      (node (ref "R3") (pin "1") (pinfunction "1_1") (pintype "passive"))
      (node (ref "R4") (pin "1") (pinfunction "1_1") (pintype "passive"))
      (node (ref "R5") (pin "1") (pinfunction "1_1") (pintype "passive"))
      (node (ref "R6") (pin "1") (pinfunction "1_1") (pintype "passive"))
      (node (ref "S1") (pin "3") (pinfunction "2_3") (pintype "passive"))
      (node (ref "S10") (pin "3") (pinfunction "2_3") (pintype "passive"))
      (node (ref "S11") (pin "3") (pinfunction "2_3") (pintype "passive"))
      (node (ref "S12") (pin "3") (pinfunction "2_3") (pintype "passive"))
      (node (ref "S2") (pin "3") (pinfunction "2_3") (pintype "passive"))
      (node (ref "S3") (pin "3") (pinfunction "2_3") (pintype "passive"))
      (node (ref "S4") (pin "3") (pinfunction "2_3") (pintype "passive"))
      (node (ref "S5") (pin "3") (pinfunction "2_3") (pintype "passive"))
      (node (ref "S6") (pin "3") (pinfunction "2_3") (pintype "passive"))
      (node (ref "S7") (pin "3") (pinfunction "2_3") (pintype "passive"))
      (node (ref "S8") (pin "3") (pinfunction "2_3") (pintype "passive"))
      (node (ref "S9") (pin "3") (pinfunction "2_3") (pintype "passive"))
      (node (ref "SH1") (pin "GND1") (pinfunction "GND1_GND1") (pintype "bidirectional"))
      (node (ref "SH1") (pin "GND_1") (pinfunction "GND_1_GND_1") (pintype "bidirectional"))
      (node (ref "SH1") (pin "GND_2") (pinfunction "GND_2_GND_2") (pintype "bidirectional"))
      (node (ref "SH1") (pin "GND_A") (pinfunction "GND_A_GND_A") (pintype "bidirectional"))
      (node (ref "SH1") (pin "GND_B") (pinfunction "GND_B_GND_B") (pintype "bidirectional"))
      (node (ref "TM1") (pin "3") (pinfunction "E_3") (pintype "passive"))
      (node (ref "TM2") (pin "3") (pinfunction "E_3") (pintype "passive"))
      (node (ref "TM3") (pin "3") (pinfunction "E_3") (pintype "passive"))
      (node (ref "TM4") (pin "3") (pinfunction "E_3") (pintype "passive"))
      (node (ref "TM5") (pin "3") (pinfunction "E_3") (pintype "passive"))
      (node (ref "TM6") (pin "3") (pinfunction "E_3") (pintype "passive"))
      (node (ref "X1") (pin "1") (pinfunction "KL_1") (pintype "passive"))
    )
    (net (code "84") (name "Net-(JP14-Pad2)") (class "Default")
      (node (ref "JP14") (pin "2") (pinfunction "2_2") (pintype "passive"))
      (node (ref "PL1") (pin "MS1") (pinfunction "MS1_MS1") (pintype "bidirectional"))
    )
    (net (code "85") (name "Net-(JP14-Pad4)") (class "Default")
      (node (ref "JP14") (pin "4") (pinfunction "4_4") (pintype "passive"))
      (node (ref "PL1") (pin "MS2") (pinfunction "MS2_MS2") (pintype "bidirectional"))
    )
    (net (code "86") (name "Net-(JP14-Pad6)") (class "Default")
      (node (ref "JP14") (pin "6") (pinfunction "6_6") (pintype "passive"))
      (node (ref "PL1") (pin "MS3") (pinfunction "MS3_MS3") (pintype "bidirectional"))
    )
    (net (code "87") (name "Net-(JP15-Pad2)") (class "Default")
      (node (ref "JP15") (pin "2") (pinfunction "2_2") (pintype "passive"))
      (node (ref "PL2") (pin "MS1") (pinfunction "MS1_MS1") (pintype "bidirectional"))
    )
    (net (code "88") (name "Net-(JP15-Pad4)") (class "Default")
      (node (ref "JP15") (pin "4") (pinfunction "4_4") (pintype "passive"))
      (node (ref "PL2") (pin "MS2") (pinfunction "MS2_MS2") (pintype "bidirectional"))
    )
    (net (code "89") (name "Net-(JP15-Pad6)") (class "Default")
      (node (ref "JP15") (pin "6") (pinfunction "6_6") (pintype "passive"))
      (node (ref "PL2") (pin "MS3") (pinfunction "MS3_MS3") (pintype "bidirectional"))
    )
    (net (code "90") (name "Net-(JP16-Pad2)") (class "Default")
      (node (ref "JP16") (pin "2") (pinfunction "2_2") (pintype "passive"))
      (node (ref "PL3") (pin "MS1") (pinfunction "MS1_MS1") (pintype "bidirectional"))
    )
    (net (code "91") (name "Net-(JP16-Pad4)") (class "Default")
      (node (ref "JP16") (pin "4") (pinfunction "4_4") (pintype "passive"))
      (node (ref "PL3") (pin "MS2") (pinfunction "MS2_MS2") (pintype "bidirectional"))
    )
    (net (code "92") (name "Net-(JP16-Pad6)") (class "Default")
      (node (ref "JP16") (pin "6") (pinfunction "6_6") (pintype "passive"))
      (node (ref "PL3") (pin "MS3") (pinfunction "MS3_MS3") (pintype "bidirectional"))
    )
    (net (code "93") (name "Net-(JP17-Pad2)") (class "Default")
      (node (ref "JP17") (pin "2") (pinfunction "2_2") (pintype "passive"))
      (node (ref "PL4") (pin "MS1") (pinfunction "MS1_MS1") (pintype "bidirectional"))
    )
    (net (code "94") (name "Net-(JP17-Pad4)") (class "Default")
      (node (ref "JP17") (pin "4") (pinfunction "4_4") (pintype "passive"))
      (node (ref "PL4") (pin "MS2") (pinfunction "MS2_MS2") (pintype "bidirectional"))
    )
    (net (code "95") (name "Net-(JP17-Pad6)") (class "Default")
      (node (ref "JP17") (pin "6") (pinfunction "6_6") (pintype "passive"))
      (node (ref "PL4") (pin "MS3") (pinfunction "MS3_MS3") (pintype "bidirectional"))
    )
    (net (code "96") (name "Net-(JP18-Pad2)") (class "Default")
      (node (ref "JP18") (pin "2") (pinfunction "2_2") (pintype "passive"))
      (node (ref "PL5") (pin "MS1") (pinfunction "MS1_MS1") (pintype "bidirectional"))
    )
    (net (code "97") (name "Net-(JP18-Pad4)") (class "Default")
      (node (ref "JP18") (pin "4") (pinfunction "4_4") (pintype "passive"))
      (node (ref "PL5") (pin "MS2") (pinfunction "MS2_MS2") (pintype "bidirectional"))
    )
    (net (code "98") (name "Net-(JP18-Pad6)") (class "Default")
      (node (ref "JP18") (pin "6") (pinfunction "6_6") (pintype "passive"))
      (node (ref "PL5") (pin "MS3") (pinfunction "MS3_MS3") (pintype "bidirectional"))
    )
    (net (code "99") (name "Net-(JP19-Pad2)") (class "Default")
      (node (ref "JP19") (pin "2") (pinfunction "2_2") (pintype "passive"))
      (node (ref "PL6") (pin "MS1") (pinfunction "MS1_MS1") (pintype "bidirectional"))
    )
    (net (code "100") (name "Net-(JP19-Pad4)") (class "Default")
      (node (ref "JP19") (pin "4") (pinfunction "4_4") (pintype "passive"))
      (node (ref "PL6") (pin "MS2") (pinfunction "MS2_MS2") (pintype "bidirectional"))
    )
    (net (code "101") (name "Net-(JP19-Pad6)") (class "Default")
      (node (ref "JP19") (pin "6") (pinfunction "6_6") (pintype "passive"))
      (node (ref "PL6") (pin "MS3") (pinfunction "MS3_MS3") (pintype "bidirectional"))
    )
    (net (code "102") (name "Net-(LED1-PadC)") (class "Default")
      (node (ref "LED1") (pin "C") (pinfunction "C_C") (pintype "passive"))
      (node (ref "R1") (pin "2") (pinfunction "2_2") (pintype "passive"))
    )
    (net (code "103") (name "Net-(LED2-PadC)") (class "Default")
      (node (ref "LED2") (pin "C") (pinfunction "C_C") (pintype "passive"))
      (node (ref "R2") (pin "2") (pinfunction "2_2") (pintype "passive"))
    )
    (net (code "104") (name "Net-(LED3-PadC)") (class "Default")
      (node (ref "LED3") (pin "C") (pinfunction "C_C") (pintype "passive"))
      (node (ref "R3") (pin "2") (pinfunction "2_2") (pintype "passive"))
    )
    (net (code "105") (name "Net-(LED4-PadC)") (class "Default")
      (node (ref "LED4") (pin "C") (pinfunction "C_C") (pintype "passive"))
      (node (ref "R4") (pin "2") (pinfunction "2_2") (pintype "passive"))
    )
    (net (code "106") (name "Net-(LED5-PadC)") (class "Default")
      (node (ref "LED5") (pin "C") (pinfunction "C_C") (pintype "passive"))
      (node (ref "R5") (pin "2") (pinfunction "2_2") (pintype "passive"))
    )
    (net (code "107") (name "Net-(LED6-PadC)") (class "Default")
      (node (ref "LED6") (pin "C") (pinfunction "C_C") (pintype "passive"))
      (node (ref "R6") (pin "2") (pinfunction "2_2") (pintype "passive"))
    )
    (net (code "108") (name "Net-(PL1-~{RST})") (class "Default")
      (node (ref "PL1") (pin "!RST") (pinfunction "~{RST}_!RST") (pintype "bidirectional"))
      (node (ref "PL1") (pin "!SLP") (pinfunction "~{SLP}_!SLP") (pintype "bidirectional"))
    )
    (net (code "109") (name "Net-(PL2-~{RST})") (class "Default")
      (node (ref "PL2") (pin "!RST") (pinfunction "~{RST}_!RST") (pintype "bidirectional"))
      (node (ref "PL2") (pin "!SLP") (pinfunction "~{SLP}_!SLP") (pintype "bidirectional"))
    )
    (net (code "110") (name "Net-(PL3-~{RST})") (class "Default")
      (node (ref "PL3") (pin "!RST") (pinfunction "~{RST}_!RST") (pintype "bidirectional"))
      (node (ref "PL3") (pin "!SLP") (pinfunction "~{SLP}_!SLP") (pintype "bidirectional"))
    )
    (net (code "111") (name "Net-(PL4-~{RST})") (class "Default")
      (node (ref "PL4") (pin "!RST") (pinfunction "~{RST}_!RST") (pintype "bidirectional"))
      (node (ref "PL4") (pin "!SLP") (pinfunction "~{SLP}_!SLP") (pintype "bidirectional"))
    )
    (net (code "112") (name "Net-(PL5-~{RST})") (class "Default")
      (node (ref "PL5") (pin "!RST") (pinfunction "~{RST}_!RST") (pintype "bidirectional"))
      (node (ref "PL5") (pin "!SLP") (pinfunction "~{SLP}_!SLP") (pintype "bidirectional"))
    )
    (net (code "113") (name "Net-(PL6-~{RST})") (class "Default")
      (node (ref "PL6") (pin "!RST") (pinfunction "~{RST}_!RST") (pintype "bidirectional"))
      (node (ref "PL6") (pin "!SLP") (pinfunction "~{SLP}_!SLP") (pintype "bidirectional"))
    )
    (net (code "114") (name "unconnected-(SH1-Pad2)") (class "Default")
      (node (ref "SH1") (pin "2") (pinfunction "2_2") (pintype "bidirectional"))
    )
    (net (code "115") (name "unconnected-(SH1-Pad3)") (class "Default")
      (node (ref "SH1") (pin "3") (pinfunction "3_3") (pintype "bidirectional"))
    )
    (net (code "116") (name "unconnected-(SH1-Pad4)") (class "Default")
      (node (ref "SH1") (pin "4") (pinfunction "4_4") (pintype "bidirectional"))
    )
    (net (code "117") (name "unconnected-(SH1-Pad5)") (class "Default")
      (node (ref "SH1") (pin "5") (pinfunction "5_5") (pintype "bidirectional"))
    )
    (net (code "118") (name "unconnected-(SH1-Pad5V_A)") (class "Default")
      (node (ref "SH1") (pin "5V_A") (pinfunction "5V_A_5V_A") (pintype "bidirectional"))
    )
    (net (code "119") (name "unconnected-(SH1-Pad5V_B)") (class "Default")
      (node (ref "SH1") (pin "5V_B") (pinfunction "5V_B_5V_B") (pintype "bidirectional"))
    )
    (net (code "120") (name "unconnected-(SH1-Pad6)") (class "Default")
      (node (ref "SH1") (pin "6") (pinfunction "6_6") (pintype "bidirectional"))
    )
    (net (code "121") (name "unconnected-(SH1-Pad7)") (class "Default")
      (node (ref "SH1") (pin "7") (pinfunction "7_7") (pintype "bidirectional"))
    )
    (net (code "122") (name "unconnected-(SH1-Pad31)") (class "Default")
      (node (ref "SH1") (pin "31") (pinfunction "31_31") (pintype "bidirectional"))
    )
    (net (code "123") (name "unconnected-(SH1-Pad44)") (class "Default")
      (node (ref "SH1") (pin "44") (pinfunction "44_44") (pintype "bidirectional"))
    )
    (net (code "124") (name "unconnected-(SH1-PadAREF)") (class "Default")
      (node (ref "SH1") (pin "AREF") (pinfunction "AREF_AREF") (pintype "bidirectional"))
    )
    (net (code "125") (name "unconnected-(SH1-PadCANRX)") (class "Default")
      (node (ref "SH1") (pin "CANRX") (pinfunction "CANRX_CANRX") (pintype "bidirectional"))
    )
    (net (code "126") (name "unconnected-(SH1-PadCANTX)") (class "Default")
      (node (ref "SH1") (pin "CANTX") (pinfunction "CANTX_CANTX") (pintype "bidirectional"))
    )
    (net (code "127") (name "unconnected-(SH1-PadDAC0)") (class "Default")
      (node (ref "SH1") (pin "DAC0") (pinfunction "DAC0_DAC0") (pintype "bidirectional"))
    )
    (net (code "128") (name "unconnected-(SH1-PadDAC1)") (class "Default")
      (node (ref "SH1") (pin "DAC1") (pinfunction "DAC1_DAC1") (pintype "bidirectional"))
    )
    (net (code "129") (name "unconnected-(SH1-PadIOREF)") (class "Default")
      (node (ref "SH1") (pin "IOREF") (pinfunction "IOREF_IOREF") (pintype "bidirectional"))
    )
    (net (code "130") (name "unconnected-(SH1-PadNC)") (class "Default")
      (node (ref "SH1") (pin "NC") (pinfunction "NC_NC") (pintype "bidirectional"))
    )
    (net (code "131") (name "unconnected-(SH1-PadRESET)") (class "Default")
      (node (ref "SH1") (pin "RESET") (pinfunction "RESET_RESET") (pintype "bidirectional"))
    )
    (net (code "132") (name "unconnected-(SH1-PadRX0)") (class "Default")
      (node (ref "SH1") (pin "RX0") (pinfunction "RX0_RX0") (pintype "bidirectional"))
    )
    (net (code "133") (name "unconnected-(SH1-PadSCL)") (class "Default")
      (node (ref "SH1") (pin "SCL") (pinfunction "SCL_SCL") (pintype "bidirectional"))
    )
    (net (code "134") (name "unconnected-(SH1-PadSCL1)") (class "Default")
      (node (ref "SH1") (pin "SCL1") (pinfunction "SCL1_SCL1") (pintype "bidirectional"))
    )
    (net (code "135") (name "unconnected-(SH1-PadSDA)") (class "Default")
      (node (ref "SH1") (pin "SDA") (pinfunction "SDA_SDA") (pintype "bidirectional"))
    )
    (net (code "136") (name "unconnected-(SH1-PadSDA1)") (class "Default")
      (node (ref "SH1") (pin "SDA1") (pinfunction "SDA1_SDA1") (pintype "bidirectional"))
    )
    (net (code "137") (name "unconnected-(SH1-PadTX0)") (class "Default")
      (node (ref "SH1") (pin "TX0") (pinfunction "TX0_TX0") (pintype "bidirectional"))
    )
    (net (code "138") (name "unconnected-(SH1-PadVIN)") (class "Default")
      (node (ref "SH1") (pin "VIN") (pinfunction "VIN_VIN") (pintype "bidirectional"))
    )
  )
)
